# quadcopter.net
KiCad netlist of a schematic drawn in EAGLE
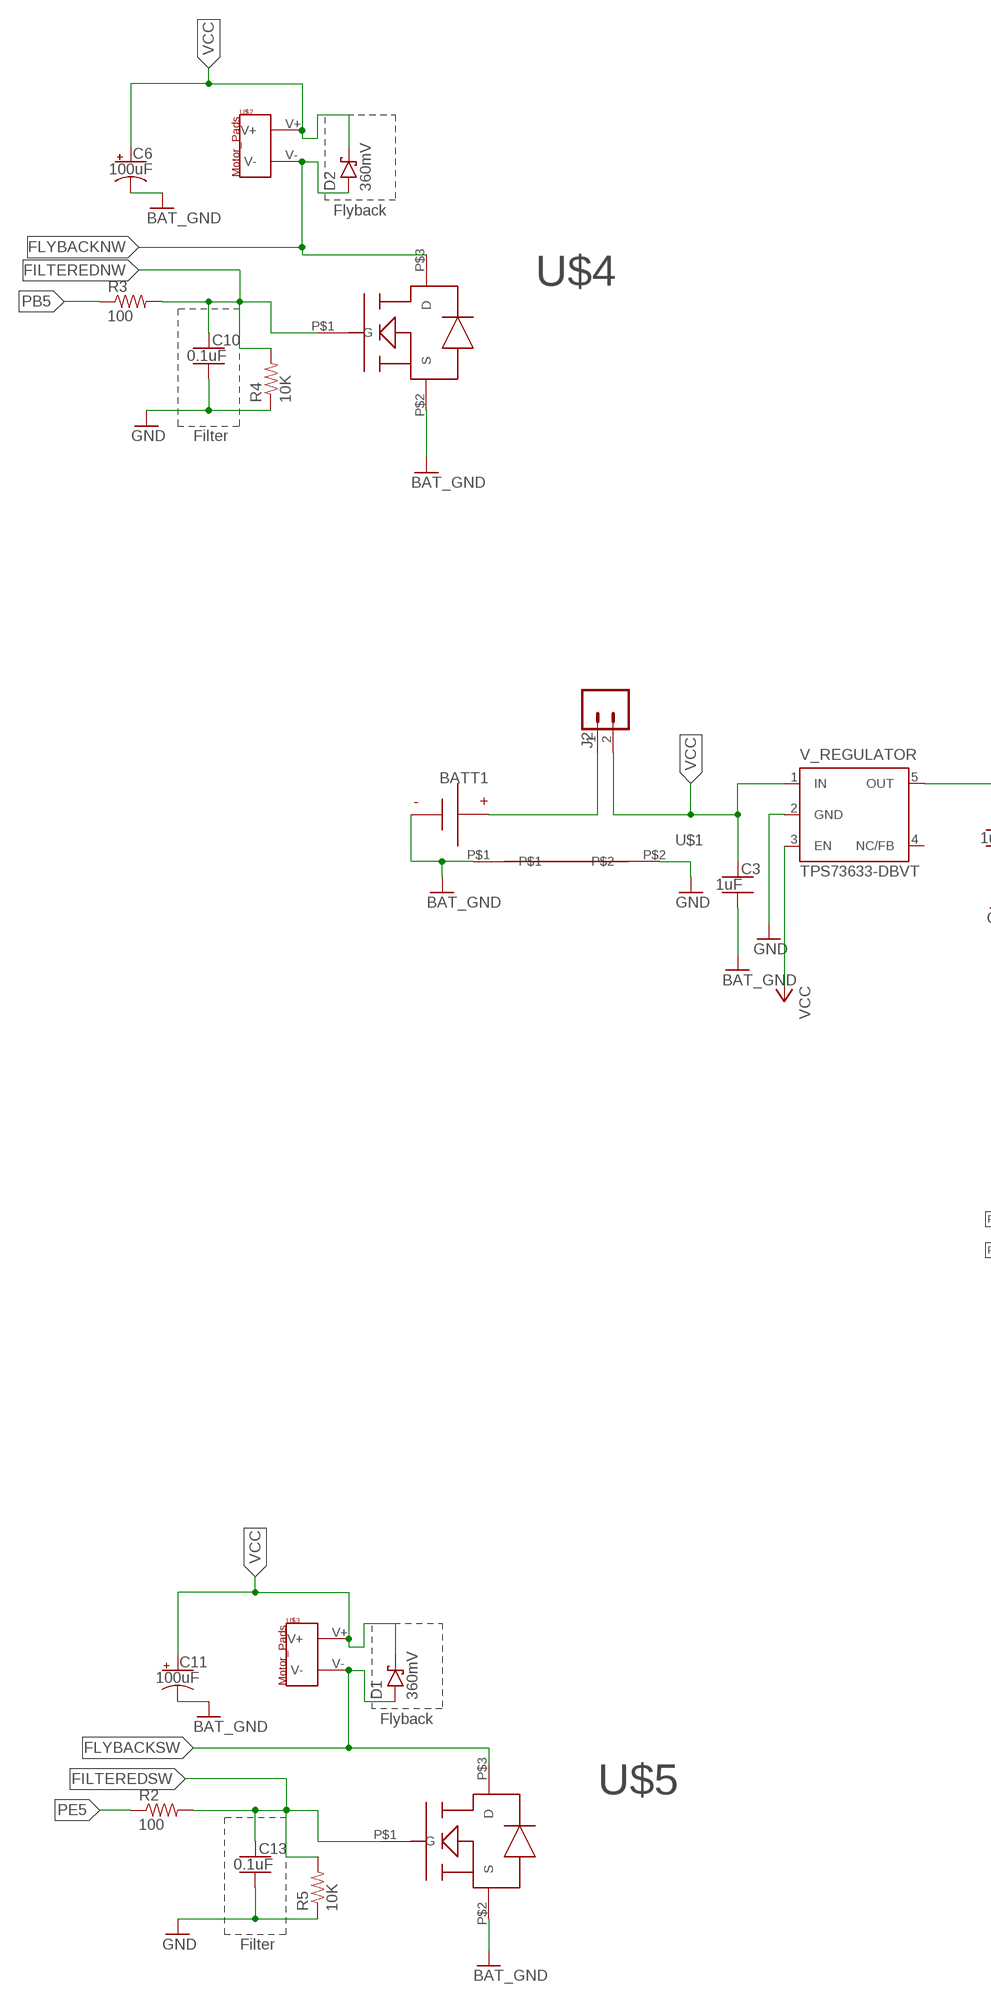
[diagram p0: schematic, sheet 1, part 1 of 2]
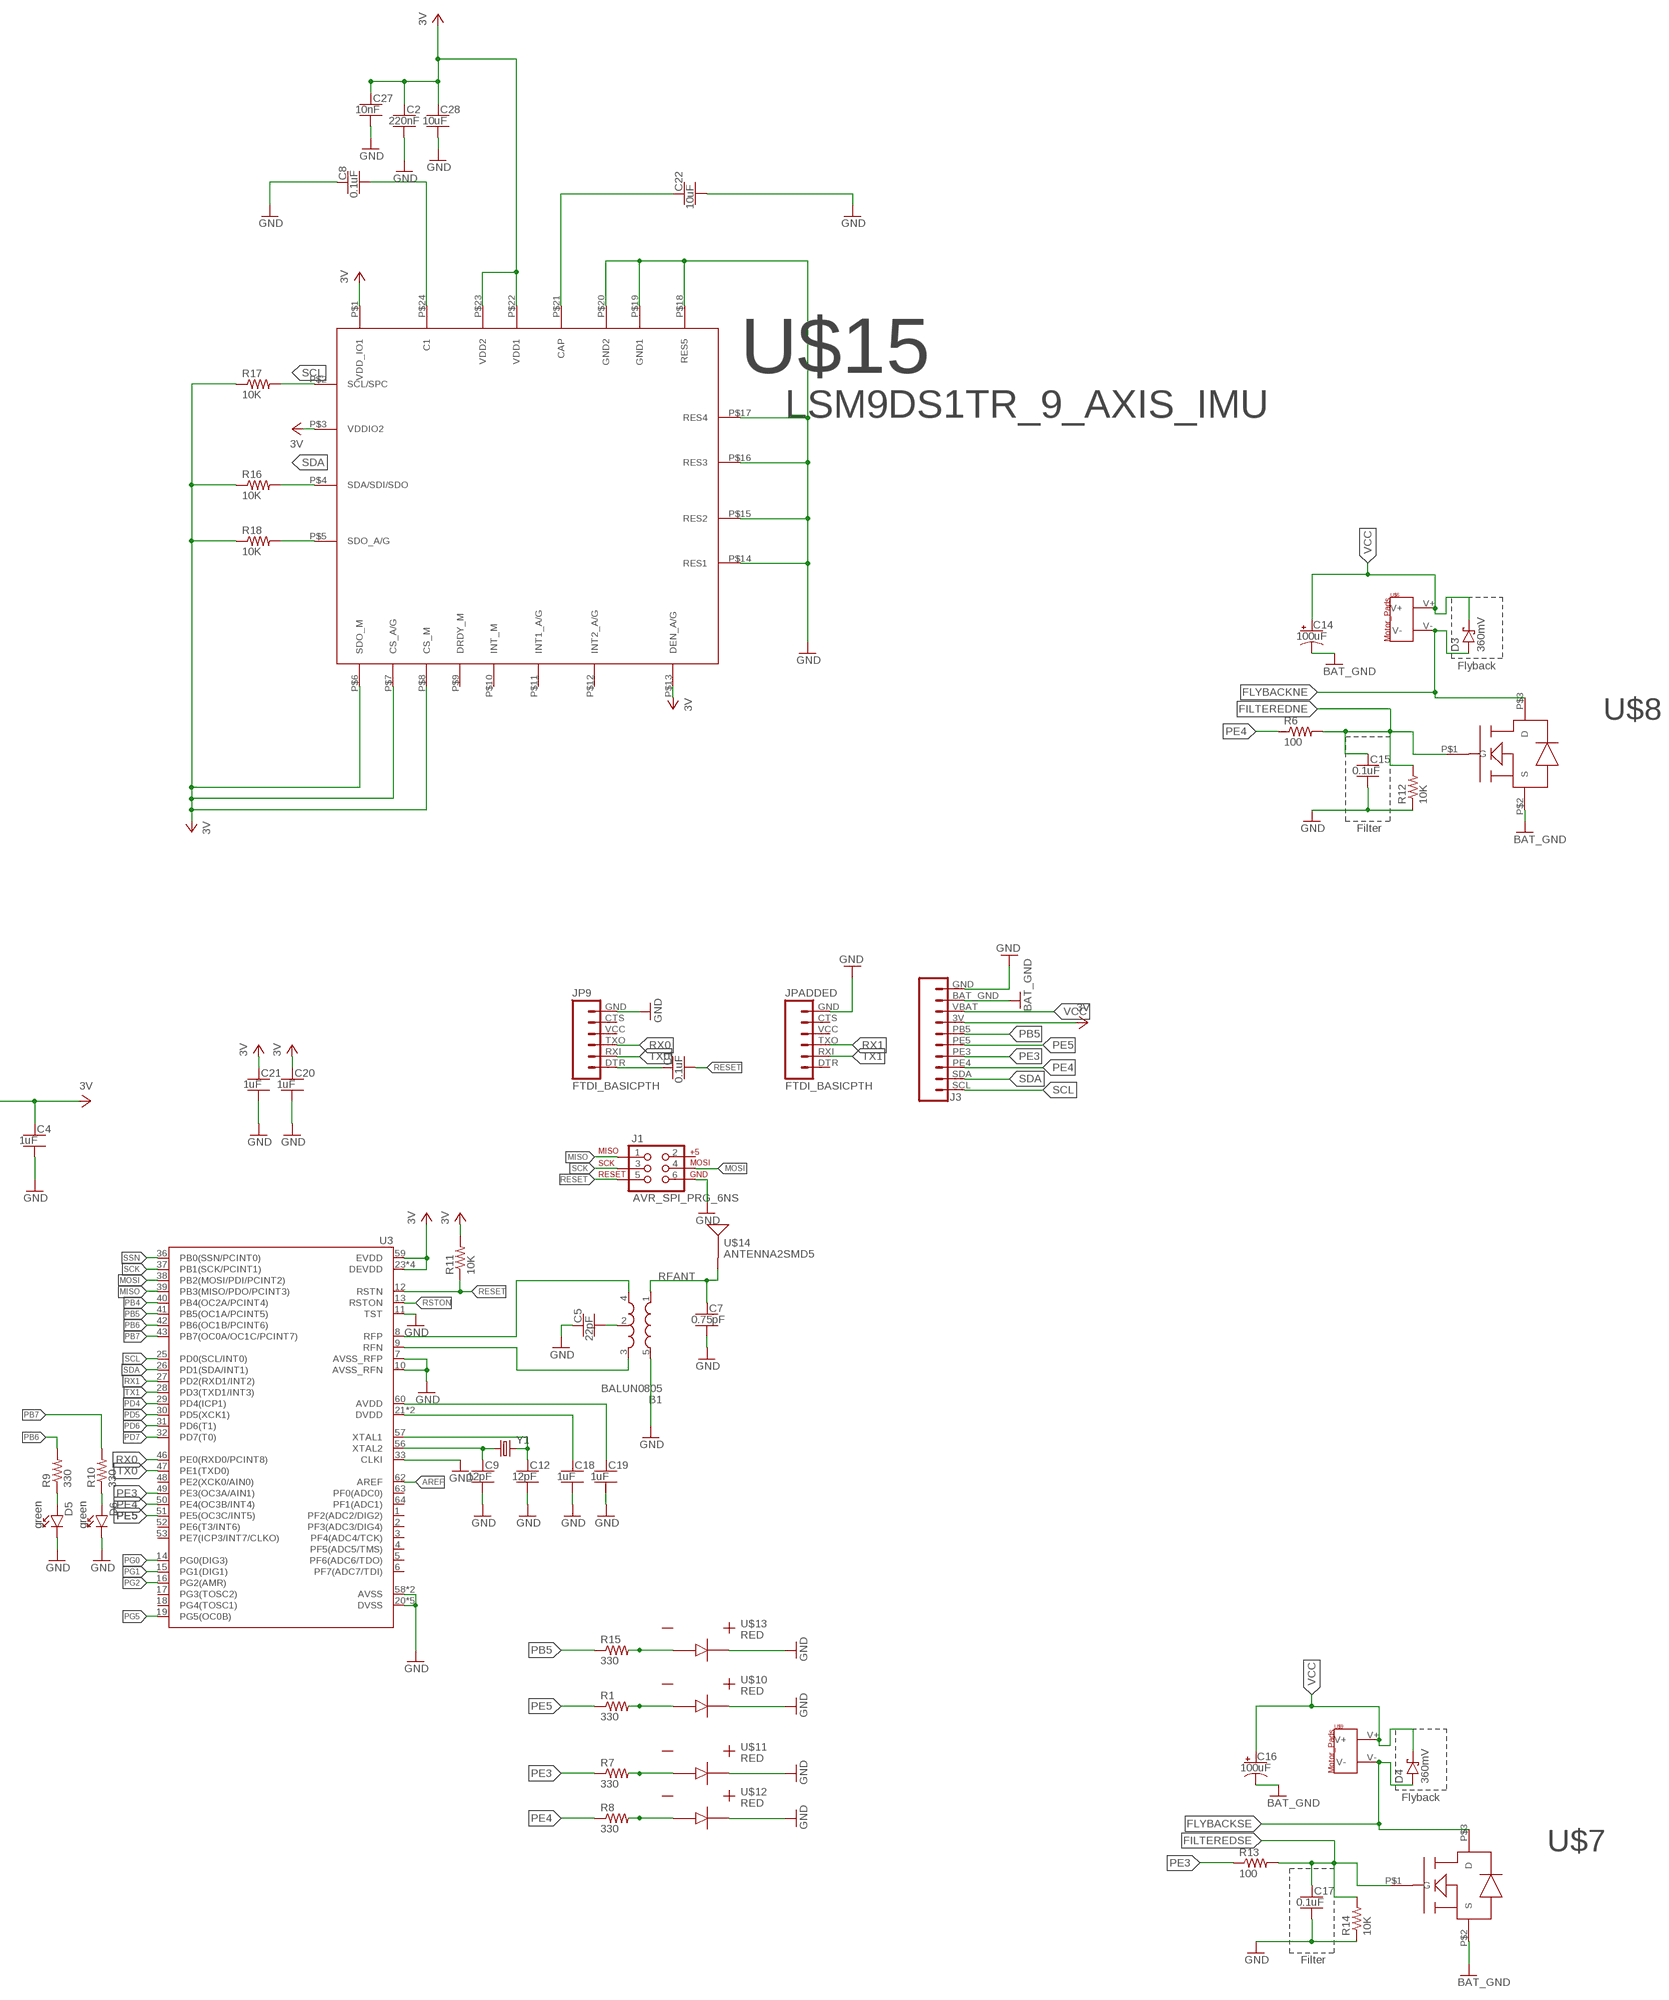
[diagram p1: schematic, sheet 1, part 2 of 2]

(export (version "E")
  (design (tool "Eeschema 10.0.6"))
  (components
    (comp (ref "B1")
      (value "BALUN0805")
      (footprint "eagle-import:BALUN")
      (fields (field (name "MFR") "Wurth Electronics Inc") (field (name "MPN") "748421245"))
      (libsource (lib "eagle-import") (part "BALUN0805"))
    )
    (comp (ref "BATT1")
      (value "BATTERY-HUBSAN-W/HOLDER")
      (footprint "eagle-import:BATTERY-W_HOLDER-380MAH-HUBSAN")
      (fields
        (field (name "MFR") "HUBSAN")
        (field (name "MPN") "X4-H107C-8-in-1")
        (field (name "CREATOR") "Swanson")
      )
      (libsource (lib "eagle-import") (part "BATTERY-HUBSAN-W/HOLDER"))
    )
    (comp (ref "C1")
      (value "0.1uF")
      (footprint "eagle-import:CAPC2012X140_HS")
      (fields
        (field (name "MFR") "Murata Electronics North America")
        (field (name "MPN") "GRM21BR71H104KA01L")
      )
      (libsource (lib "eagle-import") (part "CAPACITOR-NP_SMD-2012-0805_CERAMIC-0.1UF"))
    )
    (comp (ref "C2")
      (value "220nF")
      (footprint "eagle-import:CAPC2012X140_HS")
      (libsource (lib "eagle-import") (part "CAPACITOR-NP_SMD-2012-0805_CERAMIC"))
    )
    (comp (ref "C3")
      (value "1uF")
      (footprint "eagle-import:CAPC2012X140_HS")
      (fields
        (field (name "MFR") "Murata Electronics North America")
        (field (name "MPN") "GRM21BR71H105KA12L")
      )
      (libsource (lib "eagle-import") (part "CAPACITOR-NP_SMD-2012-0805_CERAMIC-1UF"))
    )
    (comp (ref "C4")
      (value "1uF")
      (footprint "eagle-import:CAPC2012X140_HS")
      (fields
        (field (name "MFR") "Murata Electronics North America")
        (field (name "MPN") "GRM21BR71H105KA12L")
      )
      (libsource (lib "eagle-import") (part "CAPACITOR-NP_SMD-2012-0805_CERAMIC-1UF"))
    )
    (comp (ref "C5")
      (value "22pF")
      (footprint "eagle-import:CAPC2012X140_HS")
      (fields
        (field (name "MFR") "Murata Electronics North America")
        (field (name "MPN") "GRM21A5C2E220JW01D")
      )
      (libsource (lib "eagle-import") (part "CAPACITOR-NP_SMD-2012-0805_CERAMIC-22PF"))
    )
    (comp (ref "C6")
      (value "100uF")
      (footprint "eagle-import:CAPMP7343X310_HS")
      (fields (field (name "MFR") "AVX Corporation") (field (name "MPN") "TAJD227K006RNJ"))
      (libsource (lib "eagle-import") (part "CAPACITOR-POL_SMD-7043-D_TANTALUM-220UF"))
    )
    (comp (ref "C7")
      (value "0.75pF")
      (footprint "eagle-import:CAPC2012X140_HS")
      (fields
        (field (name "MFR") "Murata Electronics North America")
        (field (name "MPN") "GQM2195C2AR75CB01D")
      )
      (libsource (lib "eagle-import") (part "CAPACITOR-NP_SMD-2012-0805_CERAMIC-0.75PF"))
    )
    (comp (ref "C8")
      (value "0.1uF")
      (footprint "eagle-import:CAPC2012X140_HS")
      (fields
        (field (name "MFR") "Murata Electronics North America")
        (field (name "MPN") "GRM21BR71H104KA01L")
      )
      (libsource (lib "eagle-import") (part "CAPACITOR-NP_SMD-2012-0805_CERAMIC-0.1UF"))
    )
    (comp (ref "C9")
      (value "12pF")
      (footprint "eagle-import:CAPC2012X140_HS")
      (fields
        (field (name "MFR") "Murata Electronics North America")
        (field (name "MPN") "GRM21A5C2E120JW01D")
      )
      (libsource (lib "eagle-import") (part "CAPACITOR-NP_SMD-2012-0805_CERAMIC-12PF"))
    )
    (comp (ref "C10")
      (value "0.1uF")
      (footprint "eagle-import:CAPC2012X140_HS")
      (fields
        (field (name "MFR") "Murata Electronics North America")
        (field (name "MPN") "GRM21BR71H105KA12L")
      )
      (libsource (lib "eagle-import") (part "CAPACITOR-NP_SMD-2012-0805_CERAMIC-1UF"))
    )
    (comp (ref "C11")
      (value "100uF")
      (footprint "eagle-import:CAPMP7343X310_HS")
      (fields (field (name "MFR") "AVX Corporation") (field (name "MPN") "TAJD227K006RNJ"))
      (libsource (lib "eagle-import") (part "CAPACITOR-POL_SMD-7043-D_TANTALUM-220UF"))
    )
    (comp (ref "C12")
      (value "12pF")
      (footprint "eagle-import:CAPC2012X140_HS")
      (fields
        (field (name "MFR") "Murata Electronics North America")
        (field (name "MPN") "GRM21A5C2E120JW01D")
      )
      (libsource (lib "eagle-import") (part "CAPACITOR-NP_SMD-2012-0805_CERAMIC-12PF"))
    )
    (comp (ref "C13")
      (value "0.1uF")
      (footprint "eagle-import:CAPC2012X140_HS")
      (fields
        (field (name "MFR") "Murata Electronics North America")
        (field (name "MPN") "GRM21BR71H105KA12L")
      )
      (libsource (lib "eagle-import") (part "CAPACITOR-NP_SMD-2012-0805_CERAMIC-1UF"))
    )
    (comp (ref "C14")
      (value "100uF")
      (footprint "eagle-import:CAPMP7343X310_HS")
      (fields (field (name "MFR") "AVX Corporation") (field (name "MPN") "TAJD227K006RNJ"))
      (libsource (lib "eagle-import") (part "CAPACITOR-POL_SMD-7043-D_TANTALUM-220UF"))
    )
    (comp (ref "C15")
      (value "0.1uF")
      (footprint "eagle-import:CAPC2012X140_HS")
      (fields
        (field (name "MFR") "Murata Electronics North America")
        (field (name "MPN") "GRM21BR71H105KA12L")
      )
      (libsource (lib "eagle-import") (part "CAPACITOR-NP_SMD-2012-0805_CERAMIC-1UF"))
    )
    (comp (ref "C16")
      (value "100uF")
      (footprint "eagle-import:CAPMP7343X310_HS")
      (fields (field (name "MFR") "AVX Corporation") (field (name "MPN") "TAJD227K006RNJ"))
      (libsource (lib "eagle-import") (part "CAPACITOR-POL_SMD-7043-D_TANTALUM-220UF"))
    )
    (comp (ref "C17")
      (value "0.1uF")
      (footprint "eagle-import:CAPC2012X140_HS")
      (fields
        (field (name "MFR") "Murata Electronics North America")
        (field (name "MPN") "GRM21BR71H105KA12L")
      )
      (libsource (lib "eagle-import") (part "CAPACITOR-NP_SMD-2012-0805_CERAMIC-1UF"))
    )
    (comp (ref "C18")
      (value "1uF")
      (footprint "eagle-import:CAPC2012X140_HS")
      (fields
        (field (name "MFR") "Murata Electronics North America")
        (field (name "MPN") "GRM21BR71H105KA12L")
      )
      (libsource (lib "eagle-import") (part "CAPACITOR-NP_SMD-2012-0805_CERAMIC-1UF"))
    )
    (comp (ref "C19")
      (value "1uF")
      (footprint "eagle-import:CAPC2012X140_HS")
      (fields
        (field (name "MFR") "Murata Electronics North America")
        (field (name "MPN") "GRM21BR71H105KA12L")
      )
      (libsource (lib "eagle-import") (part "CAPACITOR-NP_SMD-2012-0805_CERAMIC-1UF"))
    )
    (comp (ref "C20")
      (value "1uF")
      (footprint "eagle-import:CAPC2012X140_HS")
      (fields
        (field (name "MFR") "Murata Electronics North America")
        (field (name "MPN") "GRM21BR71H105KA12L")
      )
      (libsource (lib "eagle-import") (part "CAPACITOR-NP_SMD-2012-0805_CERAMIC-1UF"))
    )
    (comp (ref "C21")
      (value "1uF")
      (footprint "eagle-import:CAPC2012X140_HS")
      (fields
        (field (name "MFR") "Murata Electronics North America")
        (field (name "MPN") "GRM21BR71H105KA12L")
      )
      (libsource (lib "eagle-import") (part "CAPACITOR-NP_SMD-2012-0805_CERAMIC-1UF"))
    )
    (comp (ref "C22")
      (value "10uF")
      (footprint "eagle-import:CAPC2012X140_HS")
      (fields
        (field (name "MFR") "Murata Electronics North America")
        (field (name "MPN") "GRM21BR61E106KA73L")
      )
      (libsource (lib "eagle-import") (part "CAPACITOR-NP_SMD-2012-0805_CERAMIC-10UF"))
    )
    (comp (ref "C27")
      (value "10nF")
      (footprint "eagle-import:CAPC2012X140_HS")
      (libsource (lib "eagle-import") (part "CAPACITOR-NP_SMD-2012-0805_CERAMIC"))
    )
    (comp (ref "C28")
      (value "10uF")
      (footprint "eagle-import:CAPC2012X140_HS")
      (libsource (lib "eagle-import") (part "CAPACITOR-NP_SMD-2012-0805_CERAMIC"))
    )
    (comp (ref "D1")
      (value "360mV")
      (footprint "eagle-import:SOD3716X135_HS")
      (fields
        (field (name "MFR") "Toshiba Semiconductor and Storage")
        (field (name "MPN") "CRS08(TE85L,Q,M)")
      )
      (libsource (lib "eagle-import") (part "DIODE-SCHOTTKY_SMD-SOD123-360MV"))
    )
    (comp (ref "D2")
      (value "360mV")
      (footprint "eagle-import:SOD3716X135_HS")
      (fields
        (field (name "MFR") "Toshiba Semiconductor and Storage")
        (field (name "MPN") "CRS08(TE85L,Q,M)")
      )
      (libsource (lib "eagle-import") (part "DIODE-SCHOTTKY_SMD-SOD123-360MV"))
    )
    (comp (ref "D3")
      (value "360mV")
      (footprint "eagle-import:SOD3716X135_HS")
      (fields
        (field (name "MFR") "Toshiba Semiconductor and Storage")
        (field (name "MPN") "CRS08(TE85L,Q,M)")
      )
      (libsource (lib "eagle-import") (part "DIODE-SCHOTTKY_SMD-SOD123-360MV"))
    )
    (comp (ref "D4")
      (value "360mV")
      (footprint "eagle-import:SOD3716X135_HS")
      (fields
        (field (name "MFR") "Toshiba Semiconductor and Storage")
        (field (name "MPN") "CRS08(TE85L,Q,M)")
      )
      (libsource (lib "eagle-import") (part "DIODE-SCHOTTKY_SMD-SOD123-360MV"))
    )
    (comp (ref "D5")
      (value "green")
      (footprint "eagle-import:LEDSC125X200X120-2_HS")
      (fields (field (name "MFR") "Lite-On Inc") (field (name "MPN") "LTST-C170GKT"))
      (libsource (lib "eagle-import") (part "DIODE-LED_SMD-2012-0805-GREEN"))
    )
    (comp (ref "D6")
      (value "green")
      (footprint "eagle-import:LEDSC125X200X120-2_HS")
      (fields (field (name "MFR") "Lite-On Inc") (field (name "MPN") "LTST-C170GKT"))
      (libsource (lib "eagle-import") (part "DIODE-LED_SMD-2012-0805-GREEN"))
    )
    (comp (ref "J1")
      (value "AVR_SPI_PRG_6NS")
      (footprint "eagle-import:2X3-NS")
      (fields (field (name "MFR") "Amphenol FCI") (field (name "MPN") "67997-206HLF"))
      (libsource (lib "eagle-import") (part "AVR_SPI_PRG_6NS"))
    )
    (comp (ref "J2")
      (value "MALE_HEADER_2POS-2X1-0.1IN")
      (footprint "eagle-import:MALE_HEADER_2X1_0.1IN")
      (fields
        (field (name "MFR") "3M")
        (field (name "MPN") "961102-6404-AR")
        (field (name "CREATOR") "SWANSON")
      )
      (libsource (lib "eagle-import") (part "MALE_HEADER_2POS-2X1-0.1IN"))
    )
    (comp (ref "J3")
      (value "BREAKOUT_HEADERTH-254X10")
      (footprint "eagle-import:HDRV10W63P254_10X1_2540X254H838_HS")
      (fields (field (name "MFR") "Amphenol FCI") (field (name "MPN") "68000-110HLF"))
      (libsource (lib "eagle-import") (part "BREAKOUT_HEADERTH-254X10"))
    )
    (comp (ref "JP9")
      (value "FTDI_BASICPTH")
      (footprint "eagle-import:FTDI_BASIC")
      (fields (field (name "MFR") "Amphenol FCI") (field (name "MPN") "68016-406HLF"))
      (libsource (lib "eagle-import") (part "FTDI_BASICPTH"))
    )
    (comp (ref "JPADDED")
      (value "FTDI_BASICPTH")
      (footprint "eagle-import:FTDI_BASIC")
      (fields (field (name "MFR") "Amphenol FCI") (field (name "MPN") "68016-406HLF"))
      (libsource (lib "eagle-import") (part "FTDI_BASICPTH"))
    )
    (comp (ref "R1")
      (value "330")
      (footprint "eagle-import:RESC2012X60_HS")
      (libsource (lib "eagle-import") (part "RESISTOR_SMD-2012-0805"))
    )
    (comp (ref "R2")
      (value "100")
      (footprint "eagle-import:RESC2012X60_HS")
      (fields (field (name "MFR") "Yageo") (field (name "MPN") "RC0805JR-07100RL"))
      (libsource (lib "eagle-import") (part "RESISTOR_SMD-2012-0805-100"))
    )
    (comp (ref "R3")
      (value "100")
      (footprint "eagle-import:RESC2012X60_HS")
      (fields (field (name "MFR") "Yageo") (field (name "MPN") "RC0805JR-07100RL"))
      (libsource (lib "eagle-import") (part "RESISTOR_SMD-2012-0805-100"))
    )
    (comp (ref "R4")
      (value "10K")
      (footprint "eagle-import:RESC2012X60_HS")
      (fields (field (name "MFR") "Yageo") (field (name "MPN") "RC0805JR-0710KL"))
      (libsource (lib "eagle-import") (part "RESISTOR_SMD-2012-0805-10K"))
    )
    (comp (ref "R5")
      (value "10K")
      (footprint "eagle-import:RESC2012X60_HS")
      (fields (field (name "MFR") "Yageo") (field (name "MPN") "RC0805JR-0710KL"))
      (libsource (lib "eagle-import") (part "RESISTOR_SMD-2012-0805-10K"))
    )
    (comp (ref "R6")
      (value "100")
      (footprint "eagle-import:RESC2012X60_HS")
      (fields (field (name "MFR") "Yageo") (field (name "MPN") "RC0805JR-07100RL"))
      (libsource (lib "eagle-import") (part "RESISTOR_SMD-2012-0805-100"))
    )
    (comp (ref "R7")
      (value "330")
      (footprint "eagle-import:RESC2012X60_HS")
      (libsource (lib "eagle-import") (part "RESISTOR_SMD-2012-0805"))
    )
    (comp (ref "R8")
      (value "330")
      (footprint "eagle-import:RESC2012X60_HS")
      (libsource (lib "eagle-import") (part "RESISTOR_SMD-2012-0805"))
    )
    (comp (ref "R9")
      (value "330")
      (footprint "eagle-import:RESC2012X60_HS")
      (fields (field (name "MFR") "Yageo") (field (name "MPN") "RC0805JR-07330RL"))
      (libsource (lib "eagle-import") (part "RESISTOR_SMD-2012-0805-330"))
    )
    (comp (ref "R10")
      (value "330")
      (footprint "eagle-import:RESC2012X60_HS")
      (fields (field (name "MFR") "Yageo") (field (name "MPN") "RC0805JR-07330RL"))
      (libsource (lib "eagle-import") (part "RESISTOR_SMD-2012-0805-330"))
    )
    (comp (ref "R11")
      (value "10K")
      (footprint "eagle-import:RESC2012X60_HS")
      (fields (field (name "MFR") "Yageo") (field (name "MPN") "RC0805JR-0710KL"))
      (libsource (lib "eagle-import") (part "RESISTOR_SMD-2012-0805-10K"))
    )
    (comp (ref "R12")
      (value "10K")
      (footprint "eagle-import:RESC2012X60_HS")
      (fields (field (name "MFR") "Yageo") (field (name "MPN") "RC0805JR-0710KL"))
      (libsource (lib "eagle-import") (part "RESISTOR_SMD-2012-0805-10K"))
    )
    (comp (ref "R13")
      (value "100")
      (footprint "eagle-import:RESC2012X60_HS")
      (fields (field (name "MFR") "Yageo") (field (name "MPN") "RC0805JR-07100RL"))
      (libsource (lib "eagle-import") (part "RESISTOR_SMD-2012-0805-100"))
    )
    (comp (ref "R14")
      (value "10K")
      (footprint "eagle-import:RESC2012X60_HS")
      (fields (field (name "MFR") "Yageo") (field (name "MPN") "RC0805JR-0710KL"))
      (libsource (lib "eagle-import") (part "RESISTOR_SMD-2012-0805-10K"))
    )
    (comp (ref "R15")
      (value "330")
      (footprint "eagle-import:RESC2012X60_HS")
      (libsource (lib "eagle-import") (part "RESISTOR_SMD-2012-0805"))
    )
    (comp (ref "R16")
      (value "10K")
      (footprint "eagle-import:RESC2012X60_HS")
      (fields (field (name "MFR") "Yageo") (field (name "MPN") "RC0805JR-0710KL"))
      (libsource (lib "eagle-import") (part "RESISTOR_SMD-2012-0805-10K"))
    )
    (comp (ref "R17")
      (value "10K")
      (footprint "eagle-import:RESC2012X60_HS")
      (fields (field (name "MFR") "Yageo") (field (name "MPN") "RC0805JR-0710KL"))
      (libsource (lib "eagle-import") (part "RESISTOR_SMD-2012-0805-10K"))
    )
    (comp (ref "R18")
      (value "10K")
      (footprint "eagle-import:RESC2012X60_HS")
      (fields (field (name "MFR") "Yageo") (field (name "MPN") "RC0805JR-0710KL"))
      (libsource (lib "eagle-import") (part "RESISTOR_SMD-2012-0805-10K"))
    )
    (comp (ref "U$1")
      (value "NET_BRIDGE")
      (footprint "eagle-import:NET_BRIDGE")
      (fields (field (name "CREATOR") "BRANDON RAHMAN"))
      (libsource (lib "eagle-import") (part "NET_BRIDGE"))
    )
    (comp (ref "U$2")
      (value "MOTOR_PADS")
      (footprint "eagle-import:MOTOR_PADS")
      (fields (field (name "MFR") "NA"))
      (libsource (lib "eagle-import") (part "MOTOR_PADS"))
    )
    (comp (ref "U$3")
      (value "MOTOR_PADS")
      (footprint "eagle-import:MOTOR_PADS")
      (fields (field (name "MFR") "NA"))
      (libsource (lib "eagle-import") (part "MOTOR_PADS"))
    )
    (comp (ref "U$4")
      (value "N_CHANNEL_MOSFET")
      (footprint "eagle-import:N-CHANNEL-MOSFET")
      (fields
        (field (name "MFR") "Vishay Siliconix")
        (field (name "MPN") "SI2302CDS-T1-E3")
        (field (name "CREATOR") "Brandon Rahman")
      )
      (libsource (lib "eagle-import") (part "N_CHANNEL_MOSFET"))
    )
    (comp (ref "U$5")
      (value "N_CHANNEL_MOSFET")
      (footprint "eagle-import:N-CHANNEL-MOSFET")
      (fields
        (field (name "MFR") "Vishay Siliconix")
        (field (name "MPN") "SI2302CDS-T1-E3")
        (field (name "CREATOR") "Brandon Rahman")
      )
      (libsource (lib "eagle-import") (part "N_CHANNEL_MOSFET"))
    )
    (comp (ref "U$6")
      (value "MOTOR_PADS")
      (footprint "eagle-import:MOTOR_PADS")
      (fields (field (name "MFR") "NA"))
      (libsource (lib "eagle-import") (part "MOTOR_PADS"))
    )
    (comp (ref "U$7")
      (value "N_CHANNEL_MOSFET")
      (footprint "eagle-import:N-CHANNEL-MOSFET")
      (fields
        (field (name "MFR") "Vishay Siliconix")
        (field (name "MPN") "SI2302CDS-T1-E3")
        (field (name "CREATOR") "Brandon Rahman")
      )
      (libsource (lib "eagle-import") (part "N_CHANNEL_MOSFET"))
    )
    (comp (ref "U$8")
      (value "N_CHANNEL_MOSFET")
      (footprint "eagle-import:N-CHANNEL-MOSFET")
      (fields
        (field (name "MFR") "Vishay Siliconix")
        (field (name "MPN") "SI2302CDS-T1-E3")
        (field (name "CREATOR") "Brandon Rahman")
      )
      (libsource (lib "eagle-import") (part "N_CHANNEL_MOSFET"))
    )
    (comp (ref "U$9")
      (value "MOTOR_PADS")
      (footprint "eagle-import:MOTOR_PADS")
      (fields (field (name "MFR") "NA"))
      (libsource (lib "eagle-import") (part "MOTOR_PADS"))
    )
    (comp (ref "U$10")
      (value "RED")
      (footprint "eagle-import:RED_LED")
      (fields
        (field (name "MFR") "Cree Inc")
        (field (name "MPN") "XQARED-02-0000-000000W01 ")
        (field (name "CREATOR") "Brandon Rahman")
      )
      (libsource (lib "eagle-import") (part "RED_LED"))
    )
    (comp (ref "U$11")
      (value "RED")
      (footprint "eagle-import:RED_LED")
      (fields
        (field (name "MFR") "Cree Inc")
        (field (name "MPN") "XQARED-02-0000-000000W01 ")
        (field (name "CREATOR") "Brandon Rahman")
      )
      (libsource (lib "eagle-import") (part "RED_LED"))
    )
    (comp (ref "U$12")
      (value "RED")
      (footprint "eagle-import:RED_LED")
      (fields
        (field (name "MFR") "Cree Inc")
        (field (name "MPN") "XQARED-02-0000-000000W01 ")
        (field (name "CREATOR") "Brandon Rahman")
      )
      (libsource (lib "eagle-import") (part "RED_LED"))
    )
    (comp (ref "U$13")
      (value "RED")
      (footprint "eagle-import:RED_LED")
      (fields
        (field (name "MFR") "Cree Inc")
        (field (name "MPN") "XQARED-02-0000-000000W01 ")
        (field (name "CREATOR") "Brandon Rahman")
      )
      (libsource (lib "eagle-import") (part "RED_LED"))
    )
    (comp (ref "U$14")
      (value "ANTENNA2SMD5")
      (footprint "eagle-import:ANTENNA-CHIP5")
      (fields (field (name "MFR") "Linx Technologies Inc.") (field (name "MPN") "ANT-2.45-CHP-T"))
      (libsource (lib "eagle-import") (part "ANTENNA2SMD5"))
    )
    (comp (ref "U$15")
      (value "LSM9DS1TR_9_AXIS_IMU")
      (footprint "eagle-import:LSM9DS1TR_9_AXIS_IMU")
      (fields
        (field (name "MFR") "STMicroelectronics")
        (field (name "MPN") "LSM9DS1TR")
        (field (name "CREATOR") "Brandon Rahman")
      )
      (libsource (lib "eagle-import") (part "LSM9DS1TR_9_AXIS_IMU"))
    )
    (comp (ref "U3")
      (value "ATMEGA128RFA1")
      (footprint "eagle-import:QFN-64")
      (fields
        (field (name "MFR") "Atmel")
        (field (name "MPN") "ATMEGA128RFA1-ZUR00")
        (field (name "CREATOR") "Swanson")
      )
      (libsource (lib "eagle-import") (part "ATMEGA128RFA1"))
    )
    (comp (ref "V_REGULATOR")
      (value "TPS73633-DBVT")
      (footprint "eagle-import:SOT23-DBV")
      (fields (field (name "MFR") "Texas Instruments") (field (name "MPN") "LP3985IM5X-3.0/NOPB"))
      (libsource (lib "eagle-import") (part "TPS73633-DBVT"))
    )
    (comp (ref "Y1")
      (value "CRYSTAL5X3")
      (footprint "eagle-import:CRYSTAL-SMD-5X3")
      (fields (field (name "MFR") "Abracon LLC") (field (name "MPN") "ABM3B-16.000MHZ-B2-T"))
      (libsource (lib "eagle-import") (part "CRYSTAL5X3"))
    )
  )
  (nets
    (net (code "1") (name "/RFANT") (class "Default")
      (node (ref "B1") (pin "1") (pinfunction "IN_1") (pintype "bidirectional"))
      (node (ref "C7") (pin "1") (pinfunction "1_1") (pintype "passive"))
      (node (ref "U$14") (pin "FEED") (pinfunction "SIGNAL_FEED") (pintype "bidirectional"))
    )
    (net (code "2") (name "3V") (class "Default")
      (node (ref "C2") (pin "1") (pinfunction "1_1") (pintype "passive"))
      (node (ref "C20") (pin "1") (pinfunction "1_1") (pintype "passive"))
      (node (ref "C21") (pin "1") (pinfunction "1_1") (pintype "passive"))
      (node (ref "C27") (pin "1") (pinfunction "1_1") (pintype "passive"))
      (node (ref "C28") (pin "1") (pinfunction "1_1") (pintype "passive"))
      (node (ref "C4") (pin "1") (pinfunction "1_1") (pintype "passive"))
      (node (ref "J3") (pin "3V") (pinfunction "3V_3V") (pintype "passive"))
      (node (ref "R11") (pin "2") (pinfunction "2_2") (pintype "passive"))
      (node (ref "R16") (pin "1") (pinfunction "1_1") (pintype "passive"))
      (node (ref "R17") (pin "1") (pinfunction "1_1") (pintype "passive"))
      (node (ref "R18") (pin "1") (pinfunction "1_1") (pintype "passive"))
      (node (ref "U$15") (pin "P$1") (pinfunction "VDD_IO1_P$1") (pintype "bidirectional"))
      (node (ref "U$15") (pin "P$13") (pinfunction "DEN_A/G_P$13") (pintype "input"))
      (node (ref "U$15") (pin "P$22") (pinfunction "VDD1_P$22") (pintype "power_in"))
      (node (ref "U$15") (pin "P$23") (pinfunction "VDD2_P$23") (pintype "power_in"))
      (node (ref "U$15") (pin "P$3") (pinfunction "VDDIO2_P$3") (pintype "power_in"))
      (node (ref "U$15") (pin "P$6") (pinfunction "SDO_M_P$6") (pintype "bidirectional"))
      (node (ref "U$15") (pin "P$7") (pinfunction "CS_A/G_P$7") (pintype "input"))
      (node (ref "U$15") (pin "P$8") (pinfunction "CS_M_P$8") (pintype "input"))
      (node (ref "U3") (pin "23") (pinfunction "DEVDD_23") (pintype "bidirectional"))
      (node (ref "U3") (pin "34") (pinfunction "DEVDD_34") (pintype "bidirectional"))
      (node (ref "U3") (pin "44") (pinfunction "DEVDD_44") (pintype "bidirectional"))
      (node (ref "U3") (pin "54") (pinfunction "DEVDD_54") (pintype "bidirectional"))
      (node (ref "U3") (pin "59") (pinfunction "EVDD_59") (pintype "bidirectional"))
      (node (ref "V_REGULATOR") (pin "5") (pinfunction "OUT_5") (pintype "passive"))
    )
    (net (code "3") (name "AREF") (class "Default")
      (node (ref "U3") (pin "62") (pinfunction "AREF_62") (pintype "bidirectional"))
    )
    (net (code "4") (name "BAT_GND") (class "Default")
      (node (ref "BATT1") (pin "-") (pinfunction "N_-") (pintype "bidirectional"))
      (node (ref "C11") (pin "2") (pinfunction "-_2") (pintype "passive"))
      (node (ref "C14") (pin "2") (pinfunction "-_2") (pintype "passive"))
      (node (ref "C16") (pin "2") (pinfunction "-_2") (pintype "passive"))
      (node (ref "C3") (pin "2") (pinfunction "2_2") (pintype "passive"))
      (node (ref "C6") (pin "2") (pinfunction "-_2") (pintype "passive"))
      (node (ref "J3") (pin "BAT_GND") (pinfunction "BAT_GND_BAT_GND") (pintype "passive"))
      (node (ref "U$1") (pin "P$1") (pinfunction "P$1_P$1") (pintype "bidirectional"))
      (node (ref "U$4") (pin "P$2") (pinfunction "S_P$2") (pintype "bidirectional"))
      (node (ref "U$5") (pin "P$2") (pinfunction "S_P$2") (pintype "bidirectional"))
      (node (ref "U$7") (pin "P$2") (pinfunction "S_P$2") (pintype "bidirectional"))
      (node (ref "U$8") (pin "P$2") (pinfunction "S_P$2") (pintype "bidirectional"))
    )
    (net (code "5") (name "FILTEREDNE") (class "Default")
      (node (ref "C15") (pin "1") (pinfunction "1_1") (pintype "passive"))
      (node (ref "R12") (pin "2") (pinfunction "2_2") (pintype "passive"))
      (node (ref "R6") (pin "2") (pinfunction "2_2") (pintype "passive"))
      (node (ref "U$8") (pin "P$1") (pinfunction "G_P$1") (pintype "bidirectional"))
    )
    (net (code "6") (name "FILTEREDNW") (class "Default")
      (node (ref "C10") (pin "1") (pinfunction "1_1") (pintype "passive"))
      (node (ref "R3") (pin "2") (pinfunction "2_2") (pintype "passive"))
      (node (ref "R4") (pin "2") (pinfunction "2_2") (pintype "passive"))
      (node (ref "U$4") (pin "P$1") (pinfunction "G_P$1") (pintype "bidirectional"))
    )
    (net (code "7") (name "FILTEREDSE") (class "Default")
      (node (ref "C17") (pin "1") (pinfunction "1_1") (pintype "passive"))
      (node (ref "R13") (pin "2") (pinfunction "2_2") (pintype "passive"))
      (node (ref "R14") (pin "2") (pinfunction "2_2") (pintype "passive"))
      (node (ref "U$7") (pin "P$1") (pinfunction "G_P$1") (pintype "bidirectional"))
    )
    (net (code "8") (name "FILTEREDSW") (class "Default")
      (node (ref "C13") (pin "1") (pinfunction "1_1") (pintype "passive"))
      (node (ref "R2") (pin "2") (pinfunction "2_2") (pintype "passive"))
      (node (ref "R5") (pin "2") (pinfunction "2_2") (pintype "passive"))
      (node (ref "U$5") (pin "P$1") (pinfunction "G_P$1") (pintype "bidirectional"))
    )
    (net (code "9") (name "FLYBACKNE") (class "Default")
      (node (ref "D3") (pin "A") (pinfunction "A_A") (pintype "passive"))
      (node (ref "U$6") (pin "V-") (pinfunction "V-_V-") (pintype "bidirectional"))
      (node (ref "U$8") (pin "P$3") (pinfunction "D_P$3") (pintype "bidirectional"))
    )
    (net (code "10") (name "FLYBACKNW") (class "Default")
      (node (ref "D2") (pin "A") (pinfunction "A_A") (pintype "passive"))
      (node (ref "U$2") (pin "V-") (pinfunction "V-_V-") (pintype "bidirectional"))
      (node (ref "U$4") (pin "P$3") (pinfunction "D_P$3") (pintype "bidirectional"))
    )
    (net (code "11") (name "FLYBACKSE") (class "Default")
      (node (ref "D4") (pin "A") (pinfunction "A_A") (pintype "passive"))
      (node (ref "U$7") (pin "P$3") (pinfunction "D_P$3") (pintype "bidirectional"))
      (node (ref "U$9") (pin "V-") (pinfunction "V-_V-") (pintype "bidirectional"))
    )
    (net (code "12") (name "FLYBACKSW") (class "Default")
      (node (ref "D1") (pin "A") (pinfunction "A_A") (pintype "passive"))
      (node (ref "U$3") (pin "V-") (pinfunction "V-_V-") (pintype "bidirectional"))
      (node (ref "U$5") (pin "P$3") (pinfunction "D_P$3") (pintype "bidirectional"))
    )
    (net (code "13") (name "GND") (class "Default")
      (node (ref "B1") (pin "5") (pinfunction "GND_5") (pintype "bidirectional"))
      (node (ref "C10") (pin "2") (pinfunction "2_2") (pintype "passive"))
      (node (ref "C12") (pin "2") (pinfunction "2_2") (pintype "passive"))
      (node (ref "C13") (pin "2") (pinfunction "2_2") (pintype "passive"))
      (node (ref "C15") (pin "2") (pinfunction "2_2") (pintype "passive"))
      (node (ref "C17") (pin "2") (pinfunction "2_2") (pintype "passive"))
      (node (ref "C18") (pin "2") (pinfunction "2_2") (pintype "passive"))
      (node (ref "C19") (pin "2") (pinfunction "2_2") (pintype "passive"))
      (node (ref "C2") (pin "2") (pinfunction "2_2") (pintype "passive"))
      (node (ref "C20") (pin "2") (pinfunction "2_2") (pintype "passive"))
      (node (ref "C21") (pin "2") (pinfunction "2_2") (pintype "passive"))
      (node (ref "C22") (pin "2") (pinfunction "2_2") (pintype "passive"))
      (node (ref "C27") (pin "2") (pinfunction "2_2") (pintype "passive"))
      (node (ref "C28") (pin "2") (pinfunction "2_2") (pintype "passive"))
      (node (ref "C4") (pin "2") (pinfunction "2_2") (pintype "passive"))
      (node (ref "C5") (pin "1") (pinfunction "1_1") (pintype "passive"))
      (node (ref "C7") (pin "2") (pinfunction "2_2") (pintype "passive"))
      (node (ref "C8") (pin "1") (pinfunction "1_1") (pintype "passive"))
      (node (ref "C9") (pin "2") (pinfunction "2_2") (pintype "passive"))
      (node (ref "D5") (pin "C") (pinfunction "C_C") (pintype "passive"))
      (node (ref "D6") (pin "C") (pinfunction "C_C") (pintype "passive"))
      (node (ref "J1") (pin "6") (pinfunction "6_6") (pintype "passive"))
      (node (ref "J3") (pin "GND") (pinfunction "GND_GND") (pintype "passive"))
      (node (ref "JP9") (pin "GND") (pinfunction "6_GND") (pintype "passive"))
      (node (ref "JPADDED") (pin "GND") (pinfunction "6_GND") (pintype "passive"))
      (node (ref "R12") (pin "1") (pinfunction "1_1") (pintype "passive"))
      (node (ref "R14") (pin "1") (pinfunction "1_1") (pintype "passive"))
      (node (ref "R4") (pin "1") (pinfunction "1_1") (pintype "passive"))
      (node (ref "R5") (pin "1") (pinfunction "1_1") (pintype "passive"))
      (node (ref "U$1") (pin "P$2") (pinfunction "P$2_P$2") (pintype "bidirectional"))
      (node (ref "U$10") (pin "P$3") (pinfunction "PAS_POS_P$3") (pintype "passive"))
      (node (ref "U$11") (pin "P$3") (pinfunction "PAS_POS_P$3") (pintype "passive"))
      (node (ref "U$12") (pin "P$3") (pinfunction "PAS_POS_P$3") (pintype "passive"))
      (node (ref "U$13") (pin "P$3") (pinfunction "PAS_POS_P$3") (pintype "passive"))
      (node (ref "U$15") (pin "P$14") (pinfunction "RES1_P$14") (pintype "passive"))
      (node (ref "U$15") (pin "P$15") (pinfunction "RES2_P$15") (pintype "passive"))
      (node (ref "U$15") (pin "P$16") (pinfunction "RES3_P$16") (pintype "passive"))
      (node (ref "U$15") (pin "P$17") (pinfunction "RES4_P$17") (pintype "passive"))
      (node (ref "U$15") (pin "P$18") (pinfunction "RES5_P$18") (pintype "passive"))
      (node (ref "U$15") (pin "P$19") (pinfunction "GND1_P$19") (pintype "power_in"))
      (node (ref "U$15") (pin "P$20") (pinfunction "GND2_P$20") (pintype "power_in"))
      (node (ref "U3") (pin "10") (pinfunction "AVSS_RFN_10") (pintype "bidirectional"))
      (node (ref "U3") (pin "11") (pinfunction "TST_11") (pintype "bidirectional"))
      (node (ref "U3") (pin "20") (pinfunction "DVSS_20") (pintype "bidirectional"))
      (node (ref "U3") (pin "24") (pinfunction "DVSS_24") (pintype "bidirectional"))
      (node (ref "U3") (pin "33") (pinfunction "CLKI_33") (pintype "bidirectional"))
      (node (ref "U3") (pin "35") (pinfunction "DVSS_35") (pintype "bidirectional"))
      (node (ref "U3") (pin "45") (pinfunction "DVSS_45") (pintype "bidirectional"))
      (node (ref "U3") (pin "55") (pinfunction "DVSS_55") (pintype "bidirectional"))
      (node (ref "U3") (pin "58") (pinfunction "AVSS_58") (pintype "bidirectional"))
      (node (ref "U3") (pin "61") (pinfunction "AVSS_61") (pintype "bidirectional"))
      (node (ref "U3") (pin "7") (pinfunction "AVSS_RFP_7") (pintype "bidirectional"))
      (node (ref "V_REGULATOR") (pin "2") (pinfunction "GND_2") (pintype "input"))
    )
    (net (code "14") (name "MISO") (class "Default")
      (node (ref "J1") (pin "1") (pinfunction "1_1") (pintype "passive"))
      (node (ref "U3") (pin "39") (pinfunction "PB3(MISO/PDO/PCINT3)_39") (pintype "bidirectional"))
    )
    (net (code "15") (name "MOSI") (class "Default")
      (node (ref "J1") (pin "4") (pinfunction "4_4") (pintype "passive"))
      (node (ref "U3") (pin "38") (pinfunction "PB2(MOSI/PDI/PCINT2)_38") (pintype "bidirectional"))
    )
    (net (code "16") (name "Net-(B1-GND-Pad2)") (class "Default")
      (node (ref "B1") (pin "2") (pinfunction "GND_2") (pintype "bidirectional"))
      (node (ref "C5") (pin "2") (pinfunction "2_2") (pintype "passive"))
    )
    (net (code "17") (name "Net-(B1-OUT1)") (class "Default")
      (node (ref "B1") (pin "4") (pinfunction "OUT1_4") (pintype "bidirectional"))
      (node (ref "U3") (pin "8") (pinfunction "RFP_8") (pintype "bidirectional"))
    )
    (net (code "18") (name "Net-(B1-OUT2)") (class "Default")
      (node (ref "B1") (pin "3") (pinfunction "OUT2_3") (pintype "bidirectional"))
      (node (ref "U3") (pin "9") (pinfunction "RFN_9") (pintype "bidirectional"))
    )
    (net (code "19") (name "Net-(BATT1-P)") (class "Default")
      (node (ref "BATT1") (pin "+") (pinfunction "P_+") (pintype "bidirectional"))
      (node (ref "J2") (pin "1") (pinfunction "1_1") (pintype "passive"))
    )
    (net (code "20") (name "Net-(C18-Pad1)") (class "Default")
      (node (ref "C18") (pin "1") (pinfunction "1_1") (pintype "passive"))
      (node (ref "U3") (pin "21") (pinfunction "DVDD_21") (pintype "bidirectional"))
      (node (ref "U3") (pin "22") (pinfunction "DVDD_22") (pintype "bidirectional"))
    )
    (net (code "21") (name "Net-(D5-PadA)") (class "Default")
      (node (ref "D5") (pin "A") (pinfunction "A_A") (pintype "passive"))
      (node (ref "R9") (pin "1") (pinfunction "1_1") (pintype "passive"))
    )
    (net (code "22") (name "Net-(D6-PadA)") (class "Default")
      (node (ref "D6") (pin "A") (pinfunction "A_A") (pintype "passive"))
      (node (ref "R10") (pin "1") (pinfunction "1_1") (pintype "passive"))
    )
    (net (code "23") (name "Net-(JP9-1)") (class "Default")
      (node (ref "C1") (pin "1") (pinfunction "1_1") (pintype "passive"))
      (node (ref "JP9") (pin "DTR") (pinfunction "1_DTR") (pintype "passive"))
    )
    (net (code "24") (name "Net-(U$10-PAS_NEG)") (class "Default")
      (node (ref "R1") (pin "2") (pinfunction "2_2") (pintype "passive"))
      (node (ref "U$10") (pin "P$1") (pinfunction "PAS_NEG_P$1") (pintype "passive"))
    )
    (net (code "25") (name "Net-(U$11-PAS_NEG)") (class "Default")
      (node (ref "R7") (pin "2") (pinfunction "2_2") (pintype "passive"))
      (node (ref "U$11") (pin "P$1") (pinfunction "PAS_NEG_P$1") (pintype "passive"))
    )
    (net (code "26") (name "Net-(U$12-PAS_NEG)") (class "Default")
      (node (ref "R8") (pin "2") (pinfunction "2_2") (pintype "passive"))
      (node (ref "U$12") (pin "P$1") (pinfunction "PAS_NEG_P$1") (pintype "passive"))
    )
    (net (code "27") (name "Net-(U$13-PAS_NEG)") (class "Default")
      (node (ref "R15") (pin "2") (pinfunction "2_2") (pintype "passive"))
      (node (ref "U$13") (pin "P$1") (pinfunction "PAS_NEG_P$1") (pintype "passive"))
    )
    (net (code "28") (name "Net-(U$15-C1)") (class "Default")
      (node (ref "C8") (pin "2") (pinfunction "2_2") (pintype "passive"))
      (node (ref "U$15") (pin "P$24") (pinfunction "C1_P$24") (pintype "passive"))
    )
    (net (code "29") (name "Net-(U$15-CAP)") (class "Default")
      (node (ref "C22") (pin "1") (pinfunction "1_1") (pintype "passive"))
      (node (ref "U$15") (pin "P$21") (pinfunction "CAP_P$21") (pintype "passive"))
    )
    (net (code "30") (name "Net-(U$15-SDO_A{slash}G)") (class "Default")
      (node (ref "R18") (pin "2") (pinfunction "2_2") (pintype "passive"))
      (node (ref "U$15") (pin "P$5") (pinfunction "SDO_A/G_P$5") (pintype "bidirectional"))
    )
    (net (code "31") (name "Net-(U3-AVDD)") (class "Default")
      (node (ref "C19") (pin "1") (pinfunction "1_1") (pintype "passive"))
      (node (ref "U3") (pin "60") (pinfunction "AVDD_60") (pintype "bidirectional"))
    )
    (net (code "32") (name "Net-(U3-XTAL1)") (class "Default")
      (node (ref "C12") (pin "1") (pinfunction "1_1") (pintype "passive"))
      (node (ref "U3") (pin "57") (pinfunction "XTAL1_57") (pintype "bidirectional"))
      (node (ref "Y1") (pin "3") (pinfunction "2_3") (pintype "passive"))
    )
    (net (code "33") (name "Net-(U3-XTAL2)") (class "Default")
      (node (ref "C9") (pin "1") (pinfunction "1_1") (pintype "passive"))
      (node (ref "U3") (pin "56") (pinfunction "XTAL2_56") (pintype "bidirectional"))
      (node (ref "Y1") (pin "1") (pinfunction "1_1") (pintype "passive"))
    )
    (net (code "34") (name "PB4") (class "Default")
      (node (ref "U3") (pin "40") (pinfunction "PB4(OC2A/PCINT4)_40") (pintype "bidirectional"))
    )
    (net (code "35") (name "PB5") (class "Default")
      (node (ref "J3") (pin "PB5") (pinfunction "PB5_PB5") (pintype "passive"))
      (node (ref "R15") (pin "1") (pinfunction "1_1") (pintype "passive"))
      (node (ref "R3") (pin "1") (pinfunction "1_1") (pintype "passive"))
      (node (ref "U3") (pin "41") (pinfunction "PB5(OC1A/PCINT5)_41") (pintype "bidirectional"))
    )
    (net (code "36") (name "PB6") (class "Default")
      (node (ref "R9") (pin "2") (pinfunction "2_2") (pintype "passive"))
      (node (ref "U3") (pin "42") (pinfunction "PB6(OC1B/PCINT6)_42") (pintype "bidirectional"))
    )
    (net (code "37") (name "PB7") (class "Default")
      (node (ref "R10") (pin "2") (pinfunction "2_2") (pintype "passive"))
      (node (ref "U3") (pin "43") (pinfunction "PB7(OC0A/OC1C/PCINT7)_43") (pintype "bidirectional"))
    )
    (net (code "38") (name "PD4") (class "Default")
      (node (ref "U3") (pin "29") (pinfunction "PD4(ICP1)_29") (pintype "bidirectional"))
    )
    (net (code "39") (name "PD5") (class "Default")
      (node (ref "U3") (pin "30") (pinfunction "PD5(XCK1)_30") (pintype "bidirectional"))
    )
    (net (code "40") (name "PD6") (class "Default")
      (node (ref "U3") (pin "31") (pinfunction "PD6(T1)_31") (pintype "bidirectional"))
    )
    (net (code "41") (name "PD7") (class "Default")
      (node (ref "U3") (pin "32") (pinfunction "PD7(T0)_32") (pintype "bidirectional"))
    )
    (net (code "42") (name "PE3") (class "Default")
      (node (ref "J3") (pin "PE3") (pinfunction "PE3_PE3") (pintype "passive"))
      (node (ref "R13") (pin "1") (pinfunction "1_1") (pintype "passive"))
      (node (ref "R7") (pin "1") (pinfunction "1_1") (pintype "passive"))
      (node (ref "U3") (pin "49") (pinfunction "PE3(OC3A/AIN1)_49") (pintype "bidirectional"))
    )
    (net (code "43") (name "PE4") (class "Default")
      (node (ref "J3") (pin "PE4") (pinfunction "PE4_PE4") (pintype "passive"))
      (node (ref "R6") (pin "1") (pinfunction "1_1") (pintype "passive"))
      (node (ref "R8") (pin "1") (pinfunction "1_1") (pintype "passive"))
      (node (ref "U3") (pin "50") (pinfunction "PE4(OC3B/INT4)_50") (pintype "bidirectional"))
    )
    (net (code "44") (name "PE5") (class "Default")
      (node (ref "J3") (pin "PE5") (pinfunction "P5_PE5") (pintype "passive"))
      (node (ref "R1") (pin "1") (pinfunction "1_1") (pintype "passive"))
      (node (ref "R2") (pin "1") (pinfunction "1_1") (pintype "passive"))
      (node (ref "U3") (pin "51") (pinfunction "PE5(OC3C/INT5)_51") (pintype "bidirectional"))
    )
    (net (code "45") (name "PG0") (class "Default")
      (node (ref "U3") (pin "14") (pinfunction "PG0(DIG3)_14") (pintype "bidirectional"))
    )
    (net (code "46") (name "PG1") (class "Default")
      (node (ref "U3") (pin "15") (pinfunction "PG1(DIG1)_15") (pintype "bidirectional"))
    )
    (net (code "47") (name "PG2") (class "Default")
      (node (ref "U3") (pin "16") (pinfunction "PG2(AMR)_16") (pintype "bidirectional"))
    )
    (net (code "48") (name "PG5") (class "Default")
      (node (ref "U3") (pin "19") (pinfunction "PG5(OC0B)_19") (pintype "bidirectional"))
    )
    (net (code "49") (name "RESET") (class "Default")
      (node (ref "C1") (pin "2") (pinfunction "2_2") (pintype "passive"))
      (node (ref "J1") (pin "5") (pinfunction "5_5") (pintype "passive"))
      (node (ref "R11") (pin "1") (pinfunction "1_1") (pintype "passive"))
      (node (ref "U3") (pin "12") (pinfunction "RSTN_12") (pintype "bidirectional"))
    )
    (net (code "50") (name "RSTON") (class "Default")
      (node (ref "U3") (pin "13") (pinfunction "RSTON_13") (pintype "bidirectional"))
    )
    (net (code "51") (name "RX0") (class "Default")
      (node (ref "JP9") (pin "TXO") (pinfunction "3_TXO") (pintype "passive"))
      (node (ref "U3") (pin "46") (pinfunction "PE0(RXD0/PCINT8)_46") (pintype "bidirectional"))
    )
    (net (code "52") (name "RX1") (class "Default")
      (node (ref "JPADDED") (pin "TXO") (pinfunction "3_TXO") (pintype "passive"))
      (node (ref "U3") (pin "27") (pinfunction "PD2(RXD1/INT2)_27") (pintype "bidirectional"))
    )
    (net (code "53") (name "SCK") (class "Default")
      (node (ref "J1") (pin "3") (pinfunction "3_3") (pintype "passive"))
      (node (ref "U3") (pin "37") (pinfunction "PB1(SCK/PCINT1)_37") (pintype "bidirectional"))
    )
    (net (code "54") (name "SCL") (class "Default")
      (node (ref "J3") (pin "SCL") (pinfunction "SCL_SCL") (pintype "passive"))
      (node (ref "R17") (pin "2") (pinfunction "2_2") (pintype "passive"))
      (node (ref "U$15") (pin "P$2") (pinfunction "SCL/SPC_P$2") (pintype "input"))
      (node (ref "U3") (pin "25") (pinfunction "PD0(SCL/INT0)_25") (pintype "bidirectional"))
    )
    (net (code "55") (name "SDA") (class "Default")
      (node (ref "J3") (pin "SDA") (pinfunction "SDA_SDA") (pintype "passive"))
      (node (ref "R16") (pin "2") (pinfunction "2_2") (pintype "passive"))
      (node (ref "U$15") (pin "P$4") (pinfunction "SDA/SDI/SDO_P$4") (pintype "bidirectional"))
      (node (ref "U3") (pin "26") (pinfunction "PD1(SDA/INT1)_26") (pintype "bidirectional"))
    )
    (net (code "56") (name "SSN") (class "Default")
      (node (ref "U3") (pin "36") (pinfunction "PB0(SSN/PCINT0)_36") (pintype "bidirectional"))
    )
    (net (code "57") (name "TX0") (class "Default")
      (node (ref "JP9") (pin "RXI") (pinfunction "2_RXI") (pintype "passive"))
      (node (ref "U3") (pin "47") (pinfunction "PE1(TXD0)_47") (pintype "bidirectional"))
    )
    (net (code "58") (name "TX1") (class "Default")
      (node (ref "JPADDED") (pin "RXI") (pinfunction "2_RXI") (pintype "passive"))
      (node (ref "U3") (pin "28") (pinfunction "PD3(TXD1/INT3)_28") (pintype "bidirectional"))
    )
    (net (code "59") (name "VCC") (class "Default")
      (node (ref "C11") (pin "1") (pinfunction "+_1") (pintype "passive"))
      (node (ref "C14") (pin "1") (pinfunction "+_1") (pintype "passive"))
      (node (ref "C16") (pin "1") (pinfunction "+_1") (pintype "passive"))
      (node (ref "C3") (pin "1") (pinfunction "1_1") (pintype "passive"))
      (node (ref "C6") (pin "1") (pinfunction "+_1") (pintype "passive"))
      (node (ref "D1") (pin "C") (pinfunction "C_C") (pintype "passive"))
      (node (ref "D2") (pin "C") (pinfunction "C_C") (pintype "passive"))
      (node (ref "D3") (pin "C") (pinfunction "C_C") (pintype "passive"))
      (node (ref "D4") (pin "C") (pinfunction "C_C") (pintype "passive"))
      (node (ref "J2") (pin "2") (pinfunction "2_2") (pintype "passive"))
      (node (ref "J3") (pin "VBAT") (pinfunction "VBAT_VBAT") (pintype "passive"))
      (node (ref "U$2") (pin "V+") (pinfunction "V+_V+") (pintype "bidirectional"))
      (node (ref "U$3") (pin "V+") (pinfunction "V+_V+") (pintype "bidirectional"))
      (node (ref "U$6") (pin "V+") (pinfunction "V+_V+") (pintype "bidirectional"))
      (node (ref "U$9") (pin "V+") (pinfunction "V+_V+") (pintype "bidirectional"))
      (node (ref "V_REGULATOR") (pin "1") (pinfunction "IN_1") (pintype "input"))
      (node (ref "V_REGULATOR") (pin "3") (pinfunction "EN_3") (pintype "input"))
    )
    (net (code "60") (name "unconnected-(J1-Pad2)") (class "Default")
      (node (ref "J1") (pin "2") (pinfunction "2_2") (pintype "passive"))
    )
    (net (code "61") (name "unconnected-(JP9-4-PadVCC)") (class "Default")
      (node (ref "JP9") (pin "VCC") (pinfunction "4_VCC") (pintype "passive"))
    )
    (net (code "62") (name "unconnected-(JP9-5-PadCTS)") (class "Default")
      (node (ref "JP9") (pin "CTS") (pinfunction "5_CTS") (pintype "passive"))
    )
    (net (code "63") (name "unconnected-(JPADDED-1-PadDTR)") (class "Default")
      (node (ref "JPADDED") (pin "DTR") (pinfunction "1_DTR") (pintype "passive"))
    )
    (net (code "64") (name "unconnected-(JPADDED-4-PadVCC)") (class "Default")
      (node (ref "JPADDED") (pin "VCC") (pinfunction "4_VCC") (pintype "passive"))
    )
    (net (code "65") (name "unconnected-(JPADDED-5-PadCTS)") (class "Default")
      (node (ref "JPADDED") (pin "CTS") (pinfunction "5_CTS") (pintype "passive"))
    )
    (net (code "66") (name "unconnected-(U$15-DRDY_M-PadP$9)") (class "Default")
      (node (ref "U$15") (pin "P$9") (pinfunction "DRDY_M_P$9") (pintype "output"))
    )
    (net (code "67") (name "unconnected-(U$15-INT1_A{slash}G-PadP$11)") (class "Default")
      (node (ref "U$15") (pin "P$11") (pinfunction "INT1_A/G_P$11") (pintype "output"))
    )
    (net (code "68") (name "unconnected-(U$15-INT2_A{slash}G-PadP$12)") (class "Default")
      (node (ref "U$15") (pin "P$12") (pinfunction "INT2_A/G_P$12") (pintype "output"))
    )
    (net (code "69") (name "unconnected-(U$15-INT_M-PadP$10)") (class "Default")
      (node (ref "U$15") (pin "P$10") (pinfunction "INT_M_P$10") (pintype "output"))
    )
    (net (code "70") (name "unconnected-(U3-PE2(XCK0{slash}AIN0)-Pad48)") (class "Default")
      (node (ref "U3") (pin "48") (pinfunction "PE2(XCK0/AIN0)_48") (pintype "bidirectional"))
    )
    (net (code "71") (name "unconnected-(U3-PE6(T3{slash}INT6)-Pad52)") (class "Default")
      (node (ref "U3") (pin "52") (pinfunction "PE6(T3/INT6)_52") (pintype "bidirectional"))
    )
    (net (code "72") (name "unconnected-(U3-PE7(ICP3{slash}INT7{slash}CLKO)-Pad53)") (class "Default")
      (node (ref "U3") (pin "53") (pinfunction "PE7(ICP3/INT7/CLKO)_53") (pintype "bidirectional"))
    )
    (net (code "73") (name "unconnected-(U3-PF0(ADC0)-Pad63)") (class "Default")
      (node (ref "U3") (pin "63") (pinfunction "PF0(ADC0)_63") (pintype "bidirectional"))
    )
    (net (code "74") (name "unconnected-(U3-PF1(ADC1)-Pad64)") (class "Default")
      (node (ref "U3") (pin "64") (pinfunction "PF1(ADC1)_64") (pintype "bidirectional"))
    )
    (net (code "75") (name "unconnected-(U3-PF2(ADC2{slash}DIG2)-Pad1)") (class "Default")
      (node (ref "U3") (pin "1") (pinfunction "PF2(ADC2/DIG2)_1") (pintype "bidirectional"))
    )
    (net (code "76") (name "unconnected-(U3-PF3(ADC3{slash}DIG4)-Pad2)") (class "Default")
      (node (ref "U3") (pin "2") (pinfunction "PF3(ADC3/DIG4)_2") (pintype "bidirectional"))
    )
    (net (code "77") (name "unconnected-(U3-PF4(ADC4{slash}TCK)-Pad3)") (class "Default")
      (node (ref "U3") (pin "3") (pinfunction "PF4(ADC4/TCK)_3") (pintype "bidirectional"))
    )
    (net (code "78") (name "unconnected-(U3-PF5(ADC5{slash}TMS)-Pad4)") (class "Default")
      (node (ref "U3") (pin "4") (pinfunction "PF5(ADC5/TMS)_4") (pintype "bidirectional"))
    )
    (net (code "79") (name "unconnected-(U3-PF6(ADC6{slash}TDO)-Pad5)") (class "Default")
      (node (ref "U3") (pin "5") (pinfunction "PF6(ADC6/TDO)_5") (pintype "bidirectional"))
    )
    (net (code "80") (name "unconnected-(U3-PF7(ADC7{slash}TDI)-Pad6)") (class "Default")
      (node (ref "U3") (pin "6") (pinfunction "PF7(ADC7/TDI)_6") (pintype "bidirectional"))
    )
    (net (code "81") (name "unconnected-(U3-PG3(TOSC2)-Pad17)") (class "Default")
      (node (ref "U3") (pin "17") (pinfunction "PG3(TOSC2)_17") (pintype "bidirectional"))
    )
    (net (code "82") (name "unconnected-(U3-PG4(TOSC1)-Pad18)") (class "Default")
      (node (ref "U3") (pin "18") (pinfunction "PG4(TOSC1)_18") (pintype "bidirectional"))
    )
    (net (code "83") (name "unconnected-(V_REGULATOR-NC{slash}FB-Pad4)") (class "Default")
      (node (ref "V_REGULATOR") (pin "4") (pinfunction "NC/FB_4") (pintype "passive"))
    )
  )
)
